# ECEN403_Team_49_Schematic.net
KiCad netlist of a schematic drawn in Altium Designer
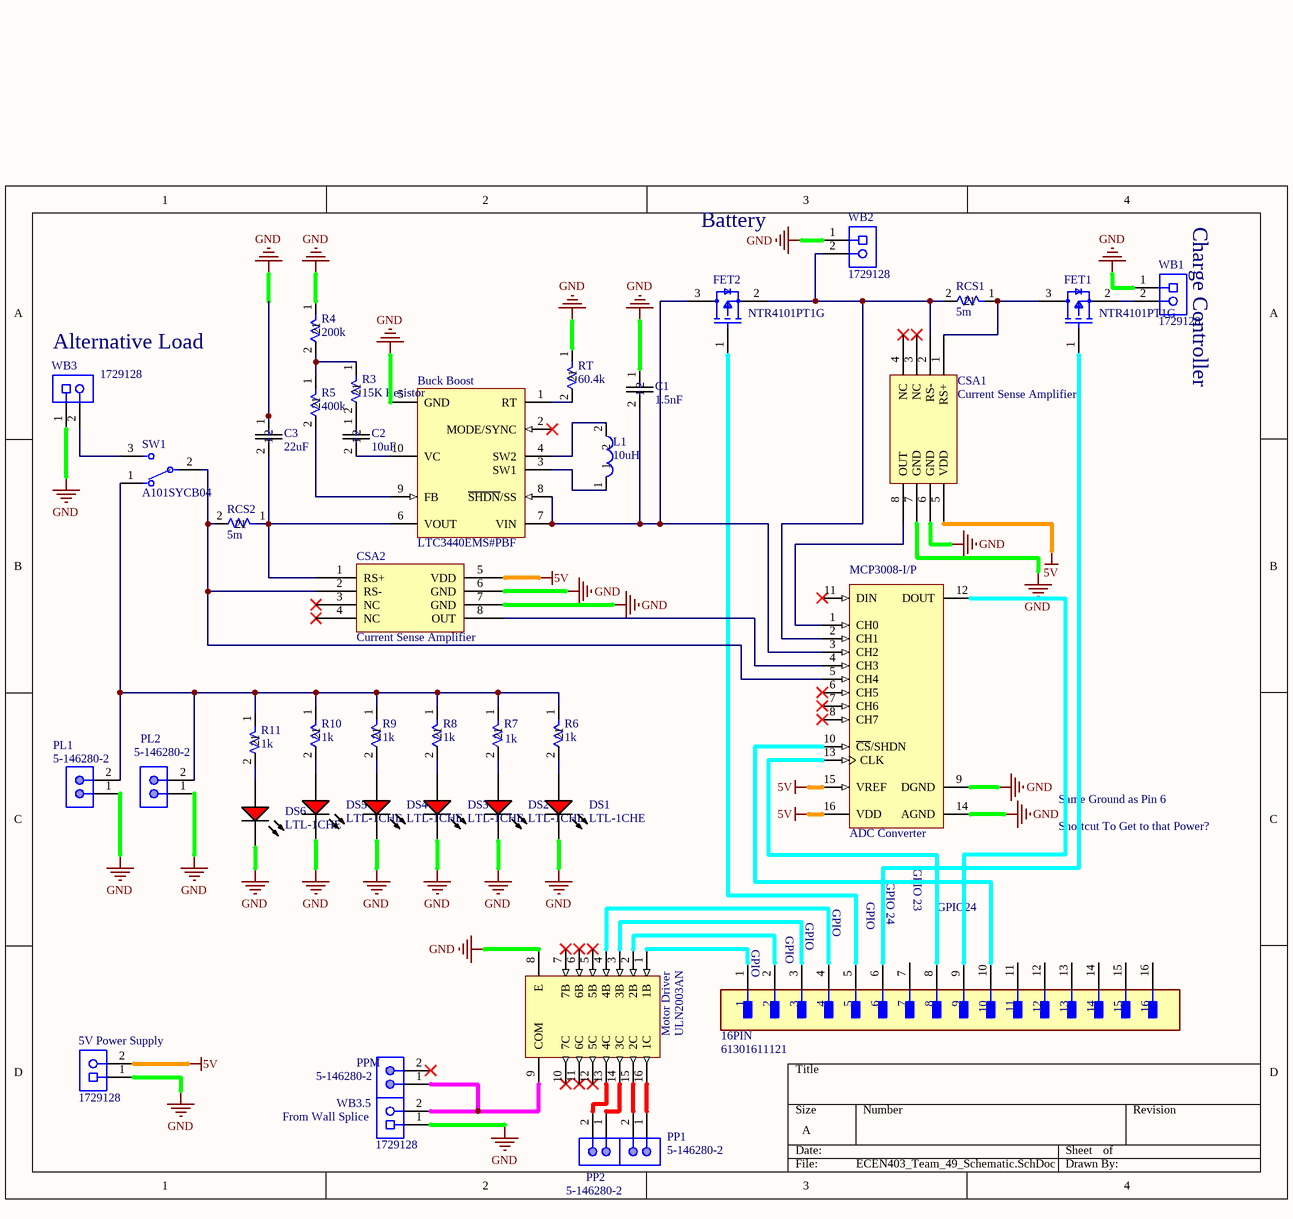
[diagram p0: ECEN403_Team_49_Schematic.SchDoc]

(export (version "E")
  (design (tool "Eeschema 10.0.6"))
  (components
    (comp (ref "5V Power Supply")
      (value "1729128")
      (footprint "Wire to board:Wire To Board")
      (description "PCB Terminal Block, 13.5 A, 400 V, 2-Pin THD, RoHS, Bulk")
      (fields (field (name "MANUFACTURER") "Phoenix Contact"))
      (libsource (lib "") (part "CMP-2000-05815-1_1"))
    )
    (comp (ref "16PIN")
      (value "61301611121")
      (footprint "16 Pin Real:16-FP-61301611121-MFG")
      (description "CONN HEADER VERT 16POS 2.54MM")
      (libsource (lib "Schematic_Library_1") (part "CMP-1502-01095-2"))
    )
    (comp (ref "ADC Converter")
      (value "MCP3008-I/P")
      (footprint "PDIP300-P16")
      (libsource (lib "Altium Content Vault") (part "CON-ADC-MCP3008-16"))
    )
    (comp (ref "Buck Boost")
      (value "LTC3440EMS#PBF")
      (footprint "LT-MS-10_M")
      (description "Micropower Synchronous Buck-Boost DC/DC Converter, 10-pin SOP (MS-10), -40 to 85 degC, Pb-Free")
      (fields (field (name "MANUFACTURER") "Linear Technology"))
      (libsource (lib "Altium Content Vault") (part "LT-LTC3440-MS-10"))
    )
    (comp (ref "C1")
      (value "1.5nF")
      (footprint "CDV19FF152JO3F:1.5nF Capacitor")
      (libsource (lib "Schematic_Library_1") (part "1.5nF"))
    )
    (comp (ref "C2")
      (value "10uF")
      (footprint "EEU-FR1H100:10uF Capacitor")
      (libsource (lib "Schematic_Library_1") (part "10uF Capacitor"))
    )
    (comp (ref "C3")
      (value "22uF")
      (footprint "MAL203851229E3:22uF Capacitor")
      (libsource (lib "Schematic_Library_1") (part "22uF Capacitor"))
    )
    (comp (ref "CSA1")
      (value "Current Sense Amplifier")
      (footprint "Current Sense Amplifier")
      (libsource (lib "Schematic_Library_1") (part "Current Sense Amplifier"))
    )
    (comp (ref "CSA2")
      (value "Current Sense Amplifier")
      (footprint "Current Sense Amplifier")
      (libsource (lib "") (part "Current Sense Amplifier_1"))
    )
    (comp (ref "DS1")
      (value "LTL-1CHE")
      (footprint "INDPR60-254-520X380X650")
      (description "Radial LED, 12.6 mcd, 20 mA, 2 V, -55 to 100 degC, 2-Pin THD, RoHS, Bulk")
      (fields (field (name "TOLERANCE") "20%"))
      (libsource (lib "Schematic_Library_1") (part "CMP-1674-00005-1"))
    )
    (comp (ref "DS2")
      (value "LTL-1CHE")
      (footprint "INDPR60-254-520X380X650")
      (description "Radial LED, 12.6 mcd, 20 mA, 2 V, -55 to 100 degC, 2-Pin THD, RoHS, Bulk")
      (fields (field (name "TOLERANCE") "20%"))
      (libsource (lib "Schematic_Library_1") (part "CMP-1674-00005-1"))
    )
    (comp (ref "DS3")
      (value "LTL-1CHE")
      (footprint "INDPR60-254-520X380X650")
      (description "Radial LED, 12.6 mcd, 20 mA, 2 V, -55 to 100 degC, 2-Pin THD, RoHS, Bulk")
      (fields (field (name "TOLERANCE") "20%"))
      (libsource (lib "Schematic_Library_1") (part "CMP-1674-00005-1"))
    )
    (comp (ref "DS4")
      (value "LTL-1CHE")
      (footprint "INDPR60-254-520X380X650")
      (description "Radial LED, 12.6 mcd, 20 mA, 2 V, -55 to 100 degC, 2-Pin THD, RoHS, Bulk")
      (fields (field (name "TOLERANCE") "20%"))
      (libsource (lib "Schematic_Library_1") (part "CMP-1674-00005-1"))
    )
    (comp (ref "DS5")
      (value "LTL-1CHE")
      (footprint "INDPR60-254-520X380X650")
      (description "Radial LED, 12.6 mcd, 20 mA, 2 V, -55 to 100 degC, 2-Pin THD, RoHS, Bulk")
      (fields (field (name "TOLERANCE") "20%"))
      (libsource (lib "Schematic_Library_1") (part "CMP-1674-00005-1"))
    )
    (comp (ref "DS6")
      (value "LTL-1CHE")
      (footprint "INDPR60-254-520X380X650")
      (description "Radial LED, 12.6 mcd, 20 mA, 2 V, -55 to 100 degC, 2-Pin THD, RoHS, Bulk")
      (fields (field (name "TOLERANCE") "20%"))
      (libsource (lib "Schematic_Library_1") (part "CMP-1674-00005-1"))
    )
    (comp (ref "FET1")
      (value "NTR4101PT1G")
      (footprint "FP-318-08-MFG")
      (description "MOSFET P-CH 20V 1.8A SOT-23")
      (libsource (lib "Altium Content Vault") (part "d54a8bb486e18a944bb8606ec07e2b8"))
    )
    (comp (ref "FET2")
      (value "NTR4101PT1G")
      (footprint "FP-318-08-MFG")
      (description "MOSFET P-CH 20V 1.8A SOT-23")
      (libsource (lib "Altium Content Vault") (part "d54a8bb486e18a944bb8606ec07e2b8"))
    )
    (comp (ref "L1")
      (value "10uH")
      (footprint "10uH Inductor")
      (libsource (lib "Schematic_Library_1") (part "10uH Inductor"))
    )
    (comp (ref "Motor Driver")
      (value "ULN2003AN")
      (footprint "N0016A")
      (fields (field (name "MANUFACTURER") "TexasInstruments"))
      (libsource (lib "Schematic_Library_1") (part "CMP-2000-07352-1"))
    )
    (comp (ref "PL1")
      (value "5-146280-2")
      (footprint "TECO-5-146280-2_V")
      (fields (field (name "MANUFACTURER") "TE Connectivity"))
      (libsource (lib "") (part "CN-1P-M-R2_1"))
    )
    (comp (ref "PL2")
      (value "5-146280-2")
      (footprint "TECO-5-146280-2_V")
      (fields (field (name "MANUFACTURER") "TE Connectivity"))
      (libsource (lib "") (part "CN-1P-M-R2_1"))
    )
    (comp (ref "PP1")
      (value "5-146280-2")
      (footprint "TECO-5-146280-2_V")
      (fields (field (name "MANUFACTURER") "TE Connectivity"))
      (libsource (lib "Altium Content Vault") (part "CN-1P-M-R2"))
    )
    (comp (ref "PP2")
      (value "5-146280-2")
      (footprint "TECO-5-146280-2_V")
      (fields (field (name "MANUFACTURER") "TE Connectivity"))
      (libsource (lib "Altium Content Vault") (part "CN-1P-M-R2"))
    )
    (comp (ref "PPM")
      (value "5-146280-2")
      (footprint "TECO-5-146280-2_V")
      (fields (field (name "MANUFACTURER") "TE Connectivity"))
      (libsource (lib "") (part "CN-1P-M-R2_1"))
    )
    (comp (ref "R3")
      (value "15K Resistor")
      (footprint "RR01J15KTB:15k Resistor")
      (libsource (lib "Schematic_Library_1") (part "15K Resistor"))
    )
    (comp (ref "R4")
      (value "200k")
      (footprint "PR01000102003JR500:200K - duplicate")
      (libsource (lib "Schematic_Library_1") (part "200k Resistor"))
    )
    (comp (ref "R5")
      (value "400k")
      (footprint "CMF60400K00BHBF:400K Resistor")
      (libsource (lib "Schematic_Library_1") (part "400k Resistor"))
    )
    (comp (ref "R6")
      (value "1k")
      (footprint "PCBComponent_1")
      (libsource (lib "Schematic_Library_1") (part "1k Resistor"))
    )
    (comp (ref "R7")
      (value "1k")
      (footprint "PCBComponent_1")
      (libsource (lib "Schematic_Library_1") (part "1k Resistor"))
    )
    (comp (ref "R8")
      (value "1k")
      (footprint "PCBComponent_1")
      (libsource (lib "Schematic_Library_1") (part "1k Resistor"))
    )
    (comp (ref "R9")
      (value "1k")
      (footprint "PCBComponent_1")
      (libsource (lib "Schematic_Library_1") (part "1k Resistor"))
    )
    (comp (ref "R10")
      (value "1k")
      (footprint "PCBComponent_1")
      (libsource (lib "Schematic_Library_1") (part "1k Resistor"))
    )
    (comp (ref "R11")
      (value "1k")
      (footprint "PCBComponent_1")
      (libsource (lib "Schematic_Library_1") (part "1k Resistor"))
    )
    (comp (ref "RCS1")
      (value "5m")
      (footprint "SR55L000FE66:Current Sense")
      (libsource (lib "Schematic_Library_1") (part "Current Sense Resistor"))
    )
    (comp (ref "RCS2")
      (value "5m")
      (footprint "SR55L000FE66:Current Sense")
      (libsource (lib "Schematic_Library_1") (part "Current Sense Resistor"))
    )
    (comp (ref "RT")
      (value "60.4k")
      (footprint "MRS2500C6042FCT00:PCBComponent_1")
      (libsource (lib "Schematic_Library_1") (part "60.4k Resistor"))
    )
    (comp (ref "SW1")
      (value "A101SYCB04")
      (footprint "FP-A101SYCB04-MFG")
      (description "SWITCH TOGGLE SPDT 0.4VA 20V")
      (libsource (lib "Altium Content Vault") (part "52c419afdc2a387c7d548259a9aeefb"))
    )
    (comp (ref "WB1")
      (value "1729128")
      (footprint "Wire to board:Wire To Board")
      (description "PCB Terminal Block, 13.5 A, 400 V, 2-Pin THD, RoHS, Bulk")
      (fields (field (name "MANUFACTURER") "Phoenix Contact"))
      (libsource (lib "Schematic_Library_1") (part "CMP-2000-05815-1"))
    )
    (comp (ref "WB2")
      (value "1729128")
      (footprint "Wire to board:Wire To Board")
      (description "PCB Terminal Block, 13.5 A, 400 V, 2-Pin THD, RoHS, Bulk")
      (fields (field (name "MANUFACTURER") "Phoenix Contact"))
      (libsource (lib "Schematic_Library_1") (part "CMP-2000-05815-1"))
    )
    (comp (ref "WB3")
      (value "1729128")
      (footprint "Wire to board:Wire To Board")
      (description "PCB Terminal Block, 13.5 A, 400 V, 2-Pin THD, RoHS, Bulk")
      (fields (field (name "MANUFACTURER") "Phoenix Contact"))
      (libsource (lib "") (part "CMP-2000-05815-1_2"))
    )
    (comp (ref "WB3.5")
      (value "1729128")
      (footprint "Wire to board:Wire To Board")
      (description "PCB Terminal Block, 13.5 A, 400 V, 2-Pin THD, RoHS, Bulk")
      (fields (field (name "MANUFACTURER") "Phoenix Contact"))
      (libsource (lib "") (part "CMP-2000-05815-1_1"))
    )
  )
  (nets
    (net (code "1") (name "5V") (class "Default")
      (node (ref "5V Power Supply") (pin "2") (pinfunction "2_2") (pintype "passive"))
      (node (ref "ADC Converter") (pin "15") (pinfunction "VREF_15") (pintype "input"))
      (node (ref "ADC Converter") (pin "16") (pinfunction "VDD_16") (pintype "power_in"))
      (node (ref "CSA1") (pin "5") (pinfunction "VDD_5") (pintype "passive"))
      (node (ref "CSA2") (pin "5") (pinfunction "VDD_5") (pintype "passive"))
    )
    (net (code "2") (name "GND") (class "Default")
      (node (ref "5V Power Supply") (pin "1") (pinfunction "1_1") (pintype "passive"))
      (node (ref "ADC Converter") (pin "14") (pinfunction "AGND_14") (pintype "power_in"))
      (node (ref "ADC Converter") (pin "9") (pinfunction "DGND_9") (pintype "power_in"))
      (node (ref "Buck Boost") (pin "5") (pinfunction "GND_5") (pintype "power_in"))
      (node (ref "C1") (pin "1") (pinfunction "1_1") (pintype "passive"))
      (node (ref "C3") (pin "1") (pinfunction "1_1") (pintype "passive"))
      (node (ref "CSA1") (pin "6") (pinfunction "GND_6") (pintype "passive"))
      (node (ref "CSA1") (pin "7") (pinfunction "GND_7") (pintype "passive"))
      (node (ref "CSA2") (pin "6") (pinfunction "GND_6") (pintype "passive"))
      (node (ref "CSA2") (pin "7") (pinfunction "GND_7") (pintype "passive"))
      (node (ref "DS1") (pin "2") (pinfunction "K_2") (pintype "passive"))
      (node (ref "DS2") (pin "2") (pinfunction "K_2") (pintype "passive"))
      (node (ref "DS3") (pin "2") (pinfunction "K_2") (pintype "passive"))
      (node (ref "DS4") (pin "2") (pinfunction "K_2") (pintype "passive"))
      (node (ref "DS5") (pin "2") (pinfunction "K_2") (pintype "passive"))
      (node (ref "DS6") (pin "2") (pinfunction "K_2") (pintype "passive"))
      (node (ref "Motor Driver") (pin "8") (pinfunction "E_8") (pintype "passive"))
      (node (ref "PL1") (pin "1") (pinfunction "1_1") (pintype "passive"))
      (node (ref "PL2") (pin "1") (pinfunction "1_1") (pintype "passive"))
      (node (ref "R4") (pin "1") (pinfunction "1_1") (pintype "passive"))
      (node (ref "RT") (pin "1") (pinfunction "1_1") (pintype "passive"))
      (node (ref "WB1") (pin "1") (pinfunction "1_1") (pintype "passive"))
      (node (ref "WB2") (pin "1") (pinfunction "1_1") (pintype "passive"))
      (node (ref "WB3") (pin "1") (pinfunction "1_1") (pintype "passive"))
      (node (ref "WB3.5") (pin "1") (pinfunction "1_1") (pintype "passive"))
    )
    (net (code "3") (name "Net-(ADC Converter-CH0)") (class "Default")
      (node (ref "ADC Converter") (pin "1") (pinfunction "CH0_1") (pintype "input"))
      (node (ref "CSA1") (pin "8") (pinfunction "OUT_8") (pintype "passive"))
    )
    (net (code "4") (name "Net-(ADC Converter-CH1)") (class "Default")
      (node (ref "ADC Converter") (pin "2") (pinfunction "CH1_2") (pintype "input"))
      (node (ref "CSA1") (pin "2") (pinfunction "RS-_2") (pintype "passive"))
      (node (ref "FET2") (pin "2") (pinfunction "Source_2") (pintype "passive"))
      (node (ref "RCS1") (pin "2") (pinfunction "2_2") (pintype "passive"))
      (node (ref "WB2") (pin "2") (pinfunction "2_2") (pintype "passive"))
    )
    (net (code "5") (name "Net-(ADC Converter-CH2)") (class "Default")
      (node (ref "ADC Converter") (pin "3") (pinfunction "CH2_3") (pintype "input"))
      (node (ref "Buck Boost") (pin "7") (pinfunction "VIN_7") (pintype "power_in"))
      (node (ref "Buck Boost") (pin "8") (pinfunction "~{SHDN}/SS_8") (pintype "input"))
      (node (ref "C1") (pin "2") (pinfunction "2_2") (pintype "passive"))
      (node (ref "FET2") (pin "3") (pinfunction "Drain_3") (pintype "passive"))
    )
    (net (code "6") (name "Net-(ADC Converter-CH3)") (class "Default")
      (node (ref "ADC Converter") (pin "4") (pinfunction "CH3_4") (pintype "input"))
      (node (ref "CSA2") (pin "8") (pinfunction "OUT_8") (pintype "passive"))
    )
    (net (code "7") (name "Net-(ADC Converter-CH4)") (class "Default")
      (node (ref "ADC Converter") (pin "5") (pinfunction "CH4_5") (pintype "input"))
      (node (ref "CSA2") (pin "2") (pinfunction "RS-_2") (pintype "passive"))
      (node (ref "RCS2") (pin "2") (pinfunction "2_2") (pintype "passive"))
      (node (ref "SW1") (pin "2") (pinfunction "2_2") (pintype "passive"))
    )
    (net (code "8") (name "Net-(ADC Converter-CLK)") (class "Default")
      (node (ref "16PIN") (pin "8") (pinfunction "8_8") (pintype "passive"))
      (node (ref "ADC Converter") (pin "13") (pinfunction "CLK_13") (pintype "input"))
    )
    (net (code "9") (name "Net-(ADC Converter-DOUT)") (class "Default")
      (node (ref "16PIN") (pin "9") (pinfunction "9_9") (pintype "passive"))
      (node (ref "ADC Converter") (pin "12") (pinfunction "DOUT_12") (pintype "tri_state"))
    )
    (net (code "10") (name "Net-(ADC Converter-~{CS}{slash}SHDN)") (class "Default")
      (node (ref "16PIN") (pin "10") (pinfunction "10_10") (pintype "passive"))
      (node (ref "ADC Converter") (pin "10") (pinfunction "~{CS}/SHDN_10") (pintype "input"))
    )
    (net (code "11") (name "Net-(Buck Boost-FB)") (class "Default")
      (node (ref "Buck Boost") (pin "9") (pinfunction "FB_9") (pintype "input"))
      (node (ref "R5") (pin "2") (pinfunction "2_2") (pintype "passive"))
    )
    (net (code "12") (name "Net-(Buck Boost-RT)") (class "Default")
      (node (ref "Buck Boost") (pin "1") (pinfunction "RT_1") (pintype "passive"))
      (node (ref "RT") (pin "2") (pinfunction "2_2") (pintype "passive"))
    )
    (net (code "13") (name "Net-(Buck Boost-SW1)") (class "Default")
      (node (ref "Buck Boost") (pin "3") (pinfunction "SW1_3") (pintype "passive"))
      (node (ref "L1") (pin "1") (pinfunction "1_1") (pintype "passive"))
    )
    (net (code "14") (name "Net-(Buck Boost-SW2)") (class "Default")
      (node (ref "Buck Boost") (pin "4") (pinfunction "SW2_4") (pintype "passive"))
      (node (ref "L1") (pin "2") (pinfunction "2_2") (pintype "passive"))
    )
    (net (code "15") (name "Net-(Buck Boost-VC)") (class "Default")
      (node (ref "Buck Boost") (pin "10") (pinfunction "VC_10") (pintype "passive"))
      (node (ref "C2") (pin "2") (pinfunction "2_2") (pintype "passive"))
    )
    (net (code "16") (name "Net-(Buck Boost-VOUT)") (class "Default")
      (node (ref "Buck Boost") (pin "6") (pinfunction "VOUT_6") (pintype "power_in"))
      (node (ref "C3") (pin "2") (pinfunction "2_2") (pintype "passive"))
      (node (ref "CSA2") (pin "1") (pinfunction "RS+_1") (pintype "passive"))
      (node (ref "RCS2") (pin "1") (pinfunction "1_1") (pintype "passive"))
    )
    (net (code "17") (name "Net-(C2-Pad1)") (class "Default")
      (node (ref "C2") (pin "1") (pinfunction "1_1") (pintype "passive"))
      (node (ref "R3") (pin "2") (pinfunction "2_2") (pintype "passive"))
    )
    (net (code "18") (name "Net-(CSA1-RS+)") (class "Default")
      (node (ref "CSA1") (pin "1") (pinfunction "RS+_1") (pintype "passive"))
      (node (ref "FET1") (pin "3") (pinfunction "Drain_3") (pintype "passive"))
      (node (ref "RCS1") (pin "1") (pinfunction "1_1") (pintype "passive"))
    )
    (net (code "19") (name "Net-(DS1-A)") (class "Default")
      (node (ref "DS1") (pin "1") (pinfunction "A_1") (pintype "passive"))
      (node (ref "R6") (pin "2") (pinfunction "2_2") (pintype "passive"))
    )
    (net (code "20") (name "Net-(DS2-A)") (class "Default")
      (node (ref "DS2") (pin "1") (pinfunction "A_1") (pintype "passive"))
      (node (ref "R7") (pin "2") (pinfunction "2_2") (pintype "passive"))
    )
    (net (code "21") (name "Net-(DS3-A)") (class "Default")
      (node (ref "DS3") (pin "1") (pinfunction "A_1") (pintype "passive"))
      (node (ref "R8") (pin "2") (pinfunction "2_2") (pintype "passive"))
    )
    (net (code "22") (name "Net-(DS4-A)") (class "Default")
      (node (ref "DS4") (pin "1") (pinfunction "A_1") (pintype "passive"))
      (node (ref "R9") (pin "2") (pinfunction "2_2") (pintype "passive"))
    )
    (net (code "23") (name "Net-(DS5-A)") (class "Default")
      (node (ref "DS5") (pin "1") (pinfunction "A_1") (pintype "passive"))
      (node (ref "R10") (pin "2") (pinfunction "2_2") (pintype "passive"))
    )
    (net (code "24") (name "Net-(DS6-A)") (class "Default")
      (node (ref "DS6") (pin "1") (pinfunction "A_1") (pintype "passive"))
      (node (ref "R11") (pin "2") (pinfunction "2_2") (pintype "passive"))
    )
    (net (code "25") (name "Net-(FET1-Gate)") (class "Default")
      (node (ref "16PIN") (pin "6") (pinfunction "6_6") (pintype "passive"))
      (node (ref "FET1") (pin "1") (pinfunction "Gate_1") (pintype "passive"))
    )
    (net (code "26") (name "Net-(FET1-Source)") (class "Default")
      (node (ref "FET1") (pin "2") (pinfunction "Source_2") (pintype "passive"))
      (node (ref "WB1") (pin "2") (pinfunction "2_2") (pintype "passive"))
    )
    (net (code "27") (name "Net-(FET2-Gate)") (class "Default")
      (node (ref "16PIN") (pin "5") (pinfunction "5_5") (pintype "passive"))
      (node (ref "FET2") (pin "1") (pinfunction "Gate_1") (pintype "passive"))
    )
    (net (code "28") (name "Net-(Motor Driver-1B)") (class "Default")
      (node (ref "16PIN") (pin "1") (pinfunction "1_1") (pintype "passive"))
      (node (ref "Motor Driver") (pin "1") (pinfunction "1B_1") (pintype "input"))
    )
    (net (code "29") (name "Net-(Motor Driver-1C)") (class "Default")
      (node (ref "Motor Driver") (pin "16") (pinfunction "1C_16") (pintype "output"))
      (node (ref "PP1") (pin "1") (pinfunction "1_1") (pintype "passive"))
    )
    (net (code "30") (name "Net-(Motor Driver-2B)") (class "Default")
      (node (ref "16PIN") (pin "2") (pinfunction "2_2") (pintype "passive"))
      (node (ref "Motor Driver") (pin "2") (pinfunction "2B_2") (pintype "input"))
    )
    (net (code "31") (name "Net-(Motor Driver-2C)") (class "Default")
      (node (ref "Motor Driver") (pin "15") (pinfunction "2C_15") (pintype "output"))
      (node (ref "PP1") (pin "2") (pinfunction "2_2") (pintype "passive"))
    )
    (net (code "32") (name "Net-(Motor Driver-3B)") (class "Default")
      (node (ref "16PIN") (pin "3") (pinfunction "3_3") (pintype "passive"))
      (node (ref "Motor Driver") (pin "3") (pinfunction "3B_3") (pintype "input"))
    )
    (net (code "33") (name "Net-(Motor Driver-3C)") (class "Default")
      (node (ref "Motor Driver") (pin "14") (pinfunction "3C_14") (pintype "output"))
      (node (ref "PP2") (pin "1") (pinfunction "1_1") (pintype "passive"))
    )
    (net (code "34") (name "Net-(Motor Driver-4B)") (class "Default")
      (node (ref "16PIN") (pin "4") (pinfunction "4_4") (pintype "passive"))
      (node (ref "Motor Driver") (pin "4") (pinfunction "4B_4") (pintype "input"))
    )
    (net (code "35") (name "Net-(Motor Driver-4C)") (class "Default")
      (node (ref "Motor Driver") (pin "13") (pinfunction "4C_13") (pintype "output"))
      (node (ref "PP2") (pin "2") (pinfunction "2_2") (pintype "passive"))
    )
    (net (code "36") (name "Net-(Motor Driver-COM)") (class "Default")
      (node (ref "Motor Driver") (pin "9") (pinfunction "COM_9") (pintype "passive"))
      (node (ref "PPM") (pin "1") (pinfunction "1_1") (pintype "passive"))
      (node (ref "WB3.5") (pin "2") (pinfunction "2_2") (pintype "passive"))
    )
    (net (code "37") (name "Net-(PL1-Pad2)") (class "Default")
      (node (ref "PL1") (pin "2") (pinfunction "2_2") (pintype "passive"))
      (node (ref "PL2") (pin "2") (pinfunction "2_2") (pintype "passive"))
      (node (ref "R10") (pin "1") (pinfunction "1_1") (pintype "passive"))
      (node (ref "R11") (pin "1") (pinfunction "1_1") (pintype "passive"))
      (node (ref "R6") (pin "1") (pinfunction "1_1") (pintype "passive"))
      (node (ref "R7") (pin "1") (pinfunction "1_1") (pintype "passive"))
      (node (ref "R8") (pin "1") (pinfunction "1_1") (pintype "passive"))
      (node (ref "R9") (pin "1") (pinfunction "1_1") (pintype "passive"))
      (node (ref "SW1") (pin "1") (pinfunction "1_1") (pintype "passive"))
    )
    (net (code "38") (name "Net-(R3-Pad1)") (class "Default")
      (node (ref "R3") (pin "1") (pinfunction "1_1") (pintype "passive"))
      (node (ref "R4") (pin "2") (pinfunction "2_2") (pintype "passive"))
      (node (ref "R5") (pin "1") (pinfunction "1_1") (pintype "passive"))
    )
    (net (code "39") (name "Net-(SW1-Pad3)") (class "Default")
      (node (ref "SW1") (pin "3") (pinfunction "3_3") (pintype "passive"))
      (node (ref "WB3") (pin "2") (pinfunction "2_2") (pintype "passive"))
    )
    (net (code "40") (name "unconnected-(16PIN-Pad7)") (class "Default")
      (node (ref "16PIN") (pin "7") (pinfunction "7_7") (pintype "passive"))
    )
    (net (code "41") (name "unconnected-(16PIN-Pad11)") (class "Default")
      (node (ref "16PIN") (pin "11") (pinfunction "11_11") (pintype "passive"))
    )
    (net (code "42") (name "unconnected-(16PIN-Pad12)") (class "Default")
      (node (ref "16PIN") (pin "12") (pinfunction "12_12") (pintype "passive"))
    )
    (net (code "43") (name "unconnected-(16PIN-Pad13)") (class "Default")
      (node (ref "16PIN") (pin "13") (pinfunction "13_13") (pintype "passive"))
    )
    (net (code "44") (name "unconnected-(16PIN-Pad14)") (class "Default")
      (node (ref "16PIN") (pin "14") (pinfunction "14_14") (pintype "passive"))
    )
    (net (code "45") (name "unconnected-(16PIN-Pad15)") (class "Default")
      (node (ref "16PIN") (pin "15") (pinfunction "15_15") (pintype "passive"))
    )
    (net (code "46") (name "unconnected-(16PIN-Pad16)") (class "Default")
      (node (ref "16PIN") (pin "16") (pinfunction "16_16") (pintype "passive"))
    )
    (net (code "47") (name "unconnected-(ADC Converter-CH5-Pad6)") (class "Default")
      (node (ref "ADC Converter") (pin "6") (pinfunction "CH5_6") (pintype "input+no_connect"))
    )
    (net (code "48") (name "unconnected-(ADC Converter-CH6-Pad7)") (class "Default")
      (node (ref "ADC Converter") (pin "7") (pinfunction "CH6_7") (pintype "input+no_connect"))
    )
    (net (code "49") (name "unconnected-(ADC Converter-CH7-Pad8)") (class "Default")
      (node (ref "ADC Converter") (pin "8") (pinfunction "CH7_8") (pintype "input+no_connect"))
    )
    (net (code "50") (name "unconnected-(ADC Converter-DIN-Pad11)") (class "Default")
      (node (ref "ADC Converter") (pin "11") (pinfunction "DIN_11") (pintype "input+no_connect"))
    )
    (net (code "51") (name "unconnected-(Buck Boost-MODE{slash}SYNC-Pad2)") (class "Default")
      (node (ref "Buck Boost") (pin "2") (pinfunction "MODE/SYNC_2") (pintype "input+no_connect"))
    )
    (net (code "52") (name "unconnected-(CSA1-NC-Pad3)") (class "Default")
      (node (ref "CSA1") (pin "3") (pinfunction "NC_3") (pintype "passive+no_connect"))
    )
    (net (code "53") (name "unconnected-(CSA1-NC-Pad4)") (class "Default")
      (node (ref "CSA1") (pin "4") (pinfunction "NC_4") (pintype "passive+no_connect"))
    )
    (net (code "54") (name "unconnected-(CSA2-NC-Pad3)") (class "Default")
      (node (ref "CSA2") (pin "3") (pinfunction "NC_3") (pintype "passive+no_connect"))
    )
    (net (code "55") (name "unconnected-(CSA2-NC-Pad4)") (class "Default")
      (node (ref "CSA2") (pin "4") (pinfunction "NC_4") (pintype "passive+no_connect"))
    )
    (net (code "56") (name "unconnected-(Motor Driver-5B-Pad5)") (class "Default")
      (node (ref "Motor Driver") (pin "5") (pinfunction "5B_5") (pintype "input+no_connect"))
    )
    (net (code "57") (name "unconnected-(Motor Driver-5C-Pad12)") (class "Default")
      (node (ref "Motor Driver") (pin "12") (pinfunction "5C_12") (pintype "output+no_connect"))
    )
    (net (code "58") (name "unconnected-(Motor Driver-6B-Pad6)") (class "Default")
      (node (ref "Motor Driver") (pin "6") (pinfunction "6B_6") (pintype "input+no_connect"))
    )
    (net (code "59") (name "unconnected-(Motor Driver-6C-Pad11)") (class "Default")
      (node (ref "Motor Driver") (pin "11") (pinfunction "6C_11") (pintype "output+no_connect"))
    )
    (net (code "60") (name "unconnected-(Motor Driver-7B-Pad7)") (class "Default")
      (node (ref "Motor Driver") (pin "7") (pinfunction "7B_7") (pintype "input+no_connect"))
    )
    (net (code "61") (name "unconnected-(Motor Driver-7C-Pad10)") (class "Default")
      (node (ref "Motor Driver") (pin "10") (pinfunction "7C_10") (pintype "output+no_connect"))
    )
    (net (code "62") (name "unconnected-(PPM-Pad2)") (class "Default")
      (node (ref "PPM") (pin "2") (pinfunction "2_2") (pintype "passive+no_connect"))
    )
  )
)
